# 2230506226.net
KiCad netlist of a schematic drawn in EasyEDA Pro
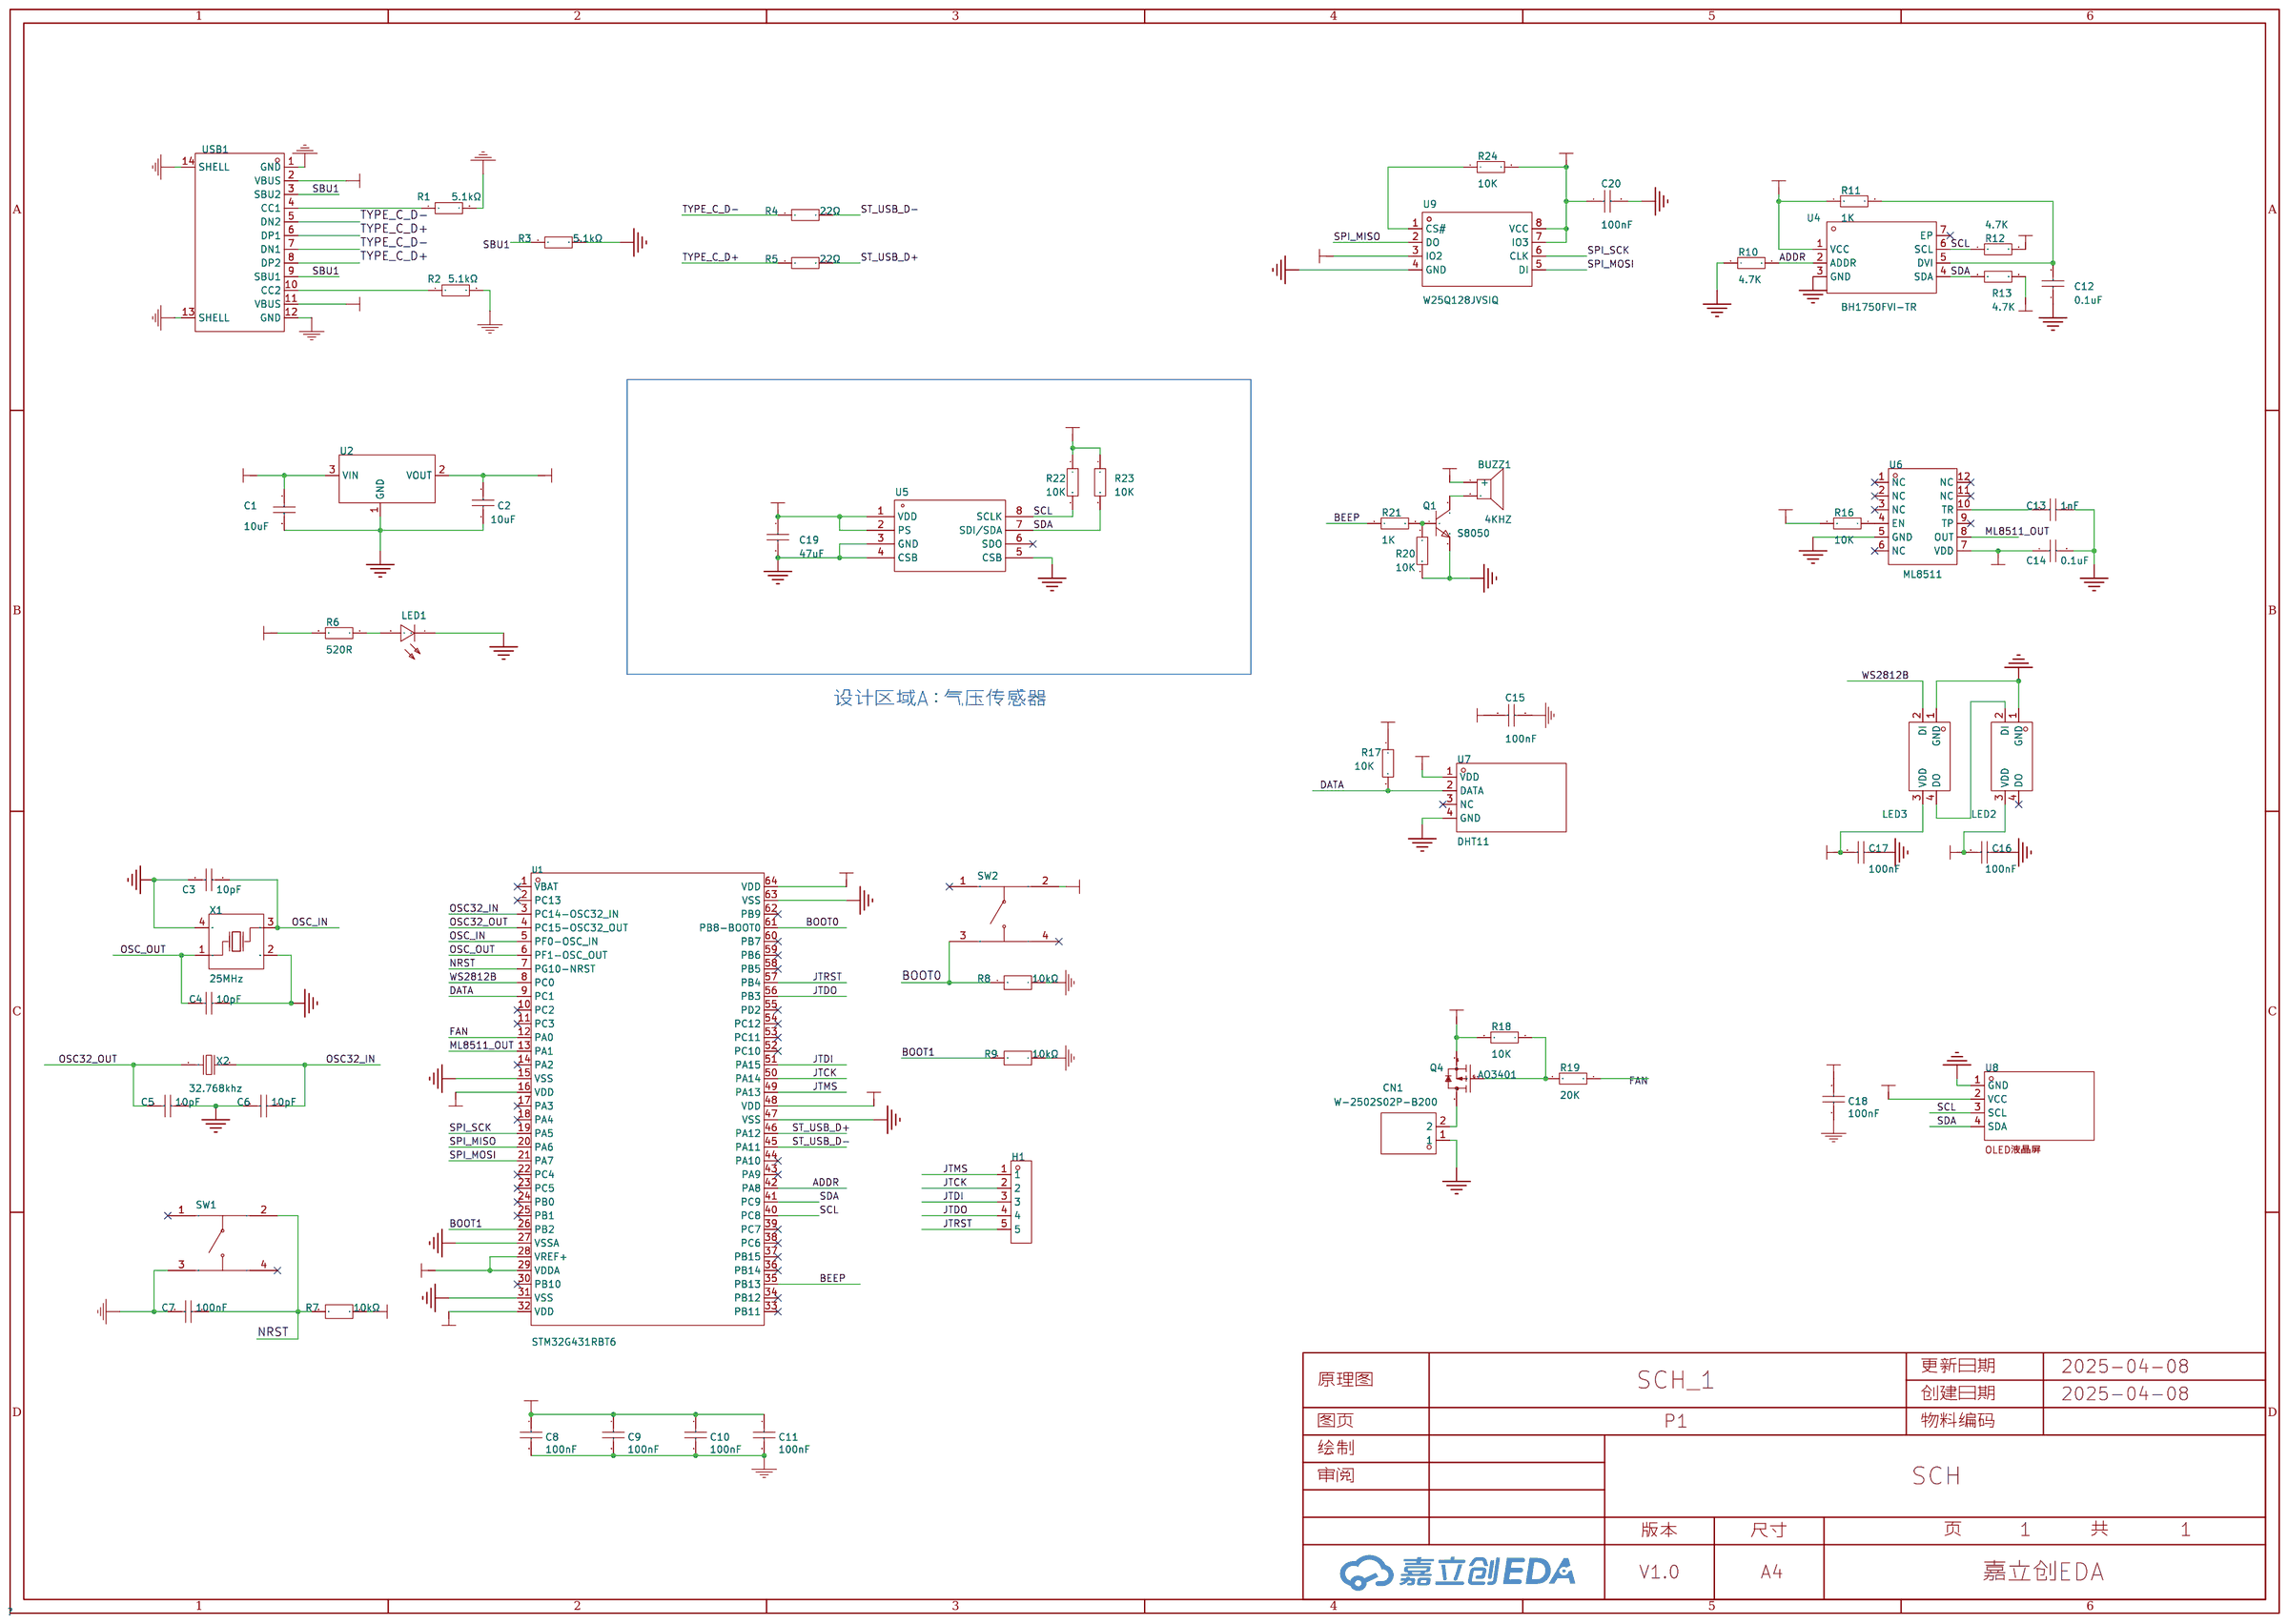
[diagram p0: schematic sheet]

(export (version "E")
  (design (tool "Eeschema 10.0.6"))
  (components
    (comp (ref "BUZZ1")
      (value "4KHZ")
      (footprint "easyedapro:BUZ-TH_BD12.0-P7.60-D0.6-FD")
      (description "驱动方式:有源(内含驱动线路);构造类型:电磁式;频率:2.7kHz;声压(SPL):85dB;")
      (fields (field (name "Manufacturer Part") "TMB12A05") (field (name "Manufacturer") "华能"))
      (libsource (lib "easyedapro") (part "TMB12A05"))
    )
    (comp (ref "C1")
      (value "10uF")
      (footprint "easyedapro:C0805")
      (description "容值:100nF;精度:±10%;额定电压:50V;材质(温度系数):X7R;")
      (fields
        (field (name "Manufacturer Part") "CC0805KRX7R9BB104")
        (field (name "Manufacturer") "YAGEO(国巨)")
      )
      (libsource (lib "easyedapro") (part "CC0805KRX7R9BB104"))
    )
    (comp (ref "C2")
      (value "10uF")
      (footprint "easyedapro:C0805")
      (description "容值:100nF;精度:±10%;额定电压:50V;材质(温度系数):X7R;")
      (fields
        (field (name "Manufacturer Part") "CC0805KRX7R9BB104")
        (field (name "Manufacturer") "YAGEO(国巨)")
      )
      (libsource (lib "easyedapro") (part "CC0805KRX7R9BB104"))
    )
    (comp (ref "C3")
      (value "10pF")
      (footprint "easyedapro:C0805")
      (description "容值:100nF;精度:±10%;额定电压:50V;材质(温度系数):X7R;")
      (fields
        (field (name "Manufacturer Part") "CC0805KRX7R9BB104")
        (field (name "Manufacturer") "YAGEO(国巨)")
      )
      (libsource (lib "easyedapro") (part "CC0805KRX7R9BB104"))
    )
    (comp (ref "C4")
      (value "10pF")
      (footprint "easyedapro:C0805")
      (description "容值:100nF;精度:±10%;额定电压:50V;材质(温度系数):X7R;")
      (fields
        (field (name "Manufacturer Part") "CC0805KRX7R9BB104")
        (field (name "Manufacturer") "YAGEO(国巨)")
      )
      (libsource (lib "easyedapro") (part "CC0805KRX7R9BB104"))
    )
    (comp (ref "C5")
      (value "10pF")
      (footprint "easyedapro:C0805")
      (description "容值:100nF;精度:±10%;额定电压:50V;材质(温度系数):X7R;")
      (fields
        (field (name "Manufacturer Part") "CC0805KRX7R9BB104")
        (field (name "Manufacturer") "YAGEO(国巨)")
      )
      (libsource (lib "easyedapro") (part "CC0805KRX7R9BB104"))
    )
    (comp (ref "C6")
      (value "10pF")
      (footprint "easyedapro:C0805")
      (description "容值:100nF;精度:±10%;额定电压:50V;材质(温度系数):X7R;")
      (fields
        (field (name "Manufacturer Part") "CC0805KRX7R9BB104")
        (field (name "Manufacturer") "YAGEO(国巨)")
      )
      (libsource (lib "easyedapro") (part "CC0805KRX7R9BB104"))
    )
    (comp (ref "C7") (value "100nF") (libsource (lib "easyedapro") (part "100nf")))
    (comp (ref "C8") (value "100nF") (libsource (lib "easyedapro") (part "100nf")))
    (comp (ref "C9") (value "100nF") (libsource (lib "easyedapro") (part "100nf")))
    (comp (ref "C10") (value "100nF") (libsource (lib "easyedapro") (part "100nf")))
    (comp (ref "C11") (value "100nF") (libsource (lib "easyedapro") (part "100nf")))
    (comp (ref "C12")
      (value "0.1uF")
      (footprint "easyedapro:C0805")
      (description "容值:100nF;精度:±10%;额定电压:50V;材质(温度系数):X7R;")
      (fields
        (field (name "Manufacturer Part") "CC0805KRX7R9BB104")
        (field (name "Manufacturer") "YAGEO(国巨)")
      )
      (libsource (lib "easyedapro") (part "CC0805KRX7R9BB104"))
    )
    (comp (ref "C13")
      (value "1nF")
      (footprint "easyedapro:C0805")
      (description "容值:100nF;精度:±10%;额定电压:50V;材质(温度系数):X7R;")
      (fields
        (field (name "Manufacturer Part") "CC0805KRX7R9BB104")
        (field (name "Manufacturer") "YAGEO(国巨)")
      )
      (libsource (lib "easyedapro") (part "CC0805KRX7R9BB104"))
    )
    (comp (ref "C14")
      (value "0.1uF")
      (footprint "easyedapro:C0805")
      (description "容值:100nF;精度:±10%;额定电压:50V;材质(温度系数):X7R;")
      (fields
        (field (name "Manufacturer Part") "CC0805KRX7R9BB104")
        (field (name "Manufacturer") "YAGEO(国巨)")
      )
      (libsource (lib "easyedapro") (part "CC0805KRX7R9BB104"))
    )
    (comp (ref "C15") (value "100nF") (libsource (lib "easyedapro") (part "100nf")))
    (comp (ref "C16")
      (value "100nF")
      (footprint "easyedapro:C0805")
      (description "容值:100nF;精度:±10%;额定电压:50V;材质(温度系数):X7R;")
      (fields
        (field (name "Manufacturer Part") "CC0805KRX7R9BB104")
        (field (name "Manufacturer") "YAGEO(国巨)")
      )
      (libsource (lib "easyedapro") (part "CC0805KRX7R9BB104"))
    )
    (comp (ref "C17")
      (value "100nF")
      (footprint "easyedapro:C0805")
      (description "容值:100nF;精度:±10%;额定电压:50V;材质(温度系数):X7R;")
      (fields
        (field (name "Manufacturer Part") "CC0805KRX7R9BB104")
        (field (name "Manufacturer") "YAGEO(国巨)")
      )
      (libsource (lib "easyedapro") (part "CC0805KRX7R9BB104"))
    )
    (comp (ref "C18") (value "100nF") (libsource (lib "easyedapro") (part "100nf")))
    (comp (ref "C19")
      (value "47uF")
      (footprint "easyedapro:C0805")
      (description "容值:100nF;精度:±10%;额定电压:50V;材质(温度系数):X7R;")
      (fields
        (field (name "Manufacturer Part") "CC0805KRX7R9BB104")
        (field (name "Manufacturer") "YAGEO(国巨)")
      )
      (libsource (lib "easyedapro") (part "CC0805KRX7R9BB104"))
    )
    (comp (ref "C20") (value "100nF") (libsource (lib "easyedapro") (part "100nf")))
    (comp (ref "CN1")
      (value "W-2502S02P-B200")
      (footprint "easyedapro:CONN-TH_2P-P2.54_2501S-2P")
      (description "插针结构:1x2P;间距:2.5mm;安装方式:-;参考系列:XH;总PIN数:2P;排数:1;每排PIN数:2;行距:-;触头材质:黄铜;")
      (fields (field (name "Manufacturer") "Ckmtw(灿科盟)"))
      (libsource (lib "easyedapro") (part "5V直流风扇"))
    )
    (comp (ref "H1")
      (value "~")
      (footprint "easyedapro:5P排针")
      (fields (field (name "Manufacturer Part") "68000-102HLF") (field (name "Manufacturer") "Amphenol ICC"))
      (libsource (lib "easyedapro") (part "5P排针"))
    )
    (comp (ref "LED1")
      (value "NCD0603R1")
      (footprint "easyedapro:LED0603-RD_RED")
      (fields (field (name "Manufacturer") "国星光电"))
      (libsource (lib "easyedapro") (part "FC-DA1608HRK-620D"))
    )
    (comp (ref "LED2")
      (value "XL-5050RGBC-WS2812B")
      (fields (field (name "Manufacturer") "XINGLIGHT(成兴光)"))
      (libsource (lib "easyedapro") (part "XL-3528RGBW-WS2812B"))
    )
    (comp (ref "LED3")
      (value "XL-5050RGBC-WS2812B")
      (fields (field (name "Manufacturer") "XINGLIGHT(成兴光)"))
      (libsource (lib "easyedapro") (part "XL-3528RGBW-WS2812B"))
    )
    (comp (ref "Q1")
      (value "S8050")
      (fields (field (name "Manufacturer") "宏迦橙"))
      (libsource (lib "easyedapro") (part "NPN"))
    )
    (comp (ref "Q4")
      (value "AO3401")
      (footprint "easyedapro:SOT-23-3_L2.9-W1.3-P1.90-LS2.4-BR")
      (fields (field (name "Manufacturer") "Hottech(合科泰)"))
      (libsource (lib "easyedapro") (part "AO3401"))
    )
    (comp (ref "R1") (value "5.1kΩ") (libsource (lib "easyedapro") (part "5.1kΩ")))
    (comp (ref "R2") (value "5.1kΩ") (libsource (lib "easyedapro") (part "5.1kΩ")))
    (comp (ref "R3") (value "5.1kΩ") (libsource (lib "easyedapro") (part "5.1kΩ")))
    (comp (ref "R4")
      (value "22Ω")
      (fields
        (field (name "Manufacturer Part") "0603WAF220JT5E")
        (field (name "Manufacturer") "UNI-ROYAL(厚声)")
      )
      (libsource (lib "easyedapro") (part "电阻"))
    )
    (comp (ref "R5")
      (value "22Ω")
      (fields
        (field (name "Manufacturer Part") "0603WAF220JT5E")
        (field (name "Manufacturer") "UNI-ROYAL(厚声)")
      )
      (libsource (lib "easyedapro") (part "电阻"))
    )
    (comp (ref "R6")
      (value "520R")
      (fields (field (name "Manufacturer Part") "RC0402FR-0710KL") (field (name "Manufacturer") "YAGEO(国巨)"))
      (libsource (lib "easyedapro") (part "电阻"))
    )
    (comp (ref "R7")
      (value "10kΩ")
      (fields (field (name "Manufacturer") "UNI-ROYAL(厚声)"))
      (libsource (lib "easyedapro") (part "10k"))
    )
    (comp (ref "R8")
      (value "10kΩ")
      (fields (field (name "Manufacturer") "UNI-ROYAL(厚声)"))
      (libsource (lib "easyedapro") (part "10k"))
    )
    (comp (ref "R9")
      (value "10kΩ")
      (fields (field (name "Manufacturer") "UNI-ROYAL(厚声)"))
      (libsource (lib "easyedapro") (part "10k"))
    )
    (comp (ref "R10")
      (value "4.7K")
      (footprint "easyedapro:R0805")
      (libsource (lib "easyedapro") (part "电阻"))
    )
    (comp (ref "R11") (value "1K") (footprint "easyedapro:R0805") (libsource (lib "easyedapro") (part "电阻")))
    (comp (ref "R12")
      (value "4.7K")
      (footprint "easyedapro:R0805")
      (libsource (lib "easyedapro") (part "电阻"))
    )
    (comp (ref "R13")
      (value "4.7K")
      (footprint "easyedapro:R0805")
      (libsource (lib "easyedapro") (part "电阻"))
    )
    (comp (ref "R16")
      (value "10K")
      (fields (field (name "Manufacturer Part") "RC0402FR-0710KL") (field (name "Manufacturer") "YAGEO(国巨)"))
      (libsource (lib "easyedapro") (part "电阻"))
    )
    (comp (ref "R17") (value "10K") (footprint "easyedapro:R0805") (libsource (lib "easyedapro") (part "电阻")))
    (comp (ref "R18") (value "10K") (footprint "easyedapro:R0805") (libsource (lib "easyedapro") (part "电阻")))
    (comp (ref "R19") (value "20K") (footprint "easyedapro:R0805") (libsource (lib "easyedapro") (part "电阻")))
    (comp (ref "R20") (value "10K") (footprint "easyedapro:R0805") (libsource (lib "easyedapro") (part "电阻")))
    (comp (ref "R21") (value "1K") (footprint "easyedapro:R0805") (libsource (lib "easyedapro") (part "电阻")))
    (comp (ref "R22") (value "10K") (footprint "easyedapro:R0805") (libsource (lib "easyedapro") (part "电阻")))
    (comp (ref "R23") (value "10K") (footprint "easyedapro:R0805") (libsource (lib "easyedapro") (part "电阻")))
    (comp (ref "R24") (value "10K") (footprint "easyedapro:R0805") (libsource (lib "easyedapro") (part "电阻")))
    (comp (ref "SW1")
      (value "TSA017A2540A07")
      (footprint "easyedapro:SW-SMD_4P-L4.2-W3.4-P2.15-LS5.2")
      (fields (field (name "Manufacturer") "BZCN(博众电气)"))
      (libsource (lib "easyedapro") (part "TSA017A2540A07"))
    )
    (comp (ref "SW2")
      (value "TSA017A2540A07")
      (footprint "easyedapro:SW-SMD_4P-L4.2-W3.4-P2.15-LS5.2")
      (fields (field (name "Manufacturer") "BZCN(博众电气)"))
      (libsource (lib "easyedapro") (part "TSA017A2540A07"))
    )
    (comp (ref "U1")
      (value "STM32G431RBT6")
      (footprint "easyedapro:LQFP-64_L10.0-W10.0-P0.50-LS12.0-BL")
      (description "CPU内核:ARM-M系列;程序存储容量:128KB;GPIO端口数量:52;工作电压范围:1.71V~3.6V;CPU最大主频:170MHz;")
      (fields (field (name "Manufacturer") "ST(意法半导体)"))
      (libsource (lib "easyedapro") (part "STM32G431RBT6"))
    )
    (comp (ref "U2")
      (value "AMS1117-3.3(XBLW)")
      (footprint "easyedapro:SOT-223-3_L6.5-W3.4-P2.30-LS7.0-BR-1")
      (description "最大输入电压:15V;输出电压:3.3V;最大输出电流:1A;电源纹波抑制比(PSRR):60dB;")
      (fields (field (name "Manufacturer") "XBLW(芯伯乐)"))
      (libsource (lib "easyedapro") (part "AMS1117-3.3(XBLW)_C18906017"))
    )
    (comp (ref "U4")
      (value "BH1750FVI-TR")
      (footprint "easyedapro:WSOF-6_L2.6-W1.6-P0.50-TL-EP")
      (description "检测颜色:-;接口类型:I2C;分辨率(位):16;")
      (fields (field (name "Manufacturer") "ROHM(罗姆)"))
      (libsource (lib "easyedapro") (part "BH1750FVI-TR"))
    )
    (comp (ref "U5") (value "~") (libsource (lib "easyedapro") (part "IC-8")))
    (comp (ref "U6")
      (value "ML8511")
      (footprint "easyedapro:DFN-12_L4.0-W3.7-P1.00-TL")
      (fields (field (name "Manufacturer") "ROHM(罗姆)"))
      (libsource (lib "easyedapro") (part "ML8511_REFBOARD"))
    )
    (comp (ref "U7")
      (value "DHT11")
      (footprint "easyedapro:SENSOR-TH_DHT11")
      (description "新款电容式数字温湿度传感器,老款已停产16.1x12.6x5.8mm")
      (fields (field (name "Manufacturer") "广州奥松"))
      (libsource (lib "easyedapro") (part "DHT11"))
    )
    (comp (ref "U8")
      (value "~")
      (footprint "easyedapro:CONN-TH_4P-P2.54_POGO-4P")
      (description "OLED液晶屏")
      (libsource (lib "easyedapro") (part "OLED液晶屏"))
    )
    (comp (ref "U9")
      (value "W25Q128JVSIQ")
      (footprint "easyedapro:SOIC-8_L5.3-W5.3-P1.27-LS8.0-BL")
      (description "存储器构架(格式):FLASH;存储器接口类型:SPI - Dual/Quad I/O;存储器容量:128Mb (16M x 8);")
      (fields (field (name "Manufacturer") "WINBOND(华邦)"))
      (libsource (lib "easyedapro") (part "W25Q128JVSIQTR"))
    )
    (comp (ref "USB1") (value "TYPE-C 16PIN 2MD(073)") (libsource (lib "easyedapro") (part "type-c 16pin")))
    (comp (ref "X1")
      (value "25MHz")
      (footprint "easyedapro:OSC-SMD_4P-L3.2-W2.5-BL")
      (description "晶振类型:贴片晶振;频率:25MHz;常温频差:±10ppm;外接负载电容:12pF;频率稳定度(全温):±20ppm;")
      (fields (field (name "Manufacturer Part") "X322525MOB4SI") (field (name "Manufacturer") "YXC(扬兴晶振)"))
      (libsource (lib "easyedapro") (part "X322525MOB4SI"))
    )
    (comp (ref "X2")
      (value "32.768kHz")
      (footprint "easyedapro:FC-135R_L3.2-W1.5")
      (description "频率:32.768kHz;晶振类型:贴片无源晶振;负载电容:12.5pF;等效串联电阻(ESR):70kΩ;频率公差:±20ppm;频率稳定度:-;工作温度:-40°C~+85°C;")
      (fields (field (name "Manufacturer Part") "Q13FC1350000400") (field (name "Manufacturer") "EPSON(爱普生)"))
      (libsource (lib "easyedapro") (part "Q13FC1350000400"))
    )
  )
  (nets
    (net (code "1") (name "/ADDR") (class "Default")
      (node (ref "R10") (pin "2") (pinfunction "2_2") (pintype "input"))
      (node (ref "U1") (pin "42") (pinfunction "PA8_42") (pintype "input"))
      (node (ref "U4") (pin "2") (pinfunction "ADDR_2") (pintype "unspecified"))
    )
    (net (code "2") (name "/BEEP") (class "Default")
      (node (ref "R21") (pin "1") (pinfunction "1_1") (pintype "input"))
      (node (ref "U1") (pin "35") (pinfunction "PB13_35") (pintype "input"))
    )
    (net (code "3") (name "/BOOT0") (class "Default")
      (node (ref "R8") (pin "2") (pinfunction "2_2") (pintype "unspecified"))
      (node (ref "SW2") (pin "3") (pinfunction "3_3") (pintype "unspecified"))
      (node (ref "U1") (pin "61") (pinfunction "PB8-BOOT0_61") (pintype "input"))
    )
    (net (code "4") (name "/BOOT1") (class "Default")
      (node (ref "R9") (pin "2") (pinfunction "2_2") (pintype "unspecified"))
      (node (ref "U1") (pin "26") (pinfunction "PB2_26") (pintype "input"))
    )
    (net (code "5") (name "/DATA") (class "Default")
      (node (ref "R17") (pin "2") (pinfunction "2_2") (pintype "input"))
      (node (ref "U1") (pin "9") (pinfunction "PC1_9") (pintype "input"))
      (node (ref "U7") (pin "2") (pinfunction "DATA_2") (pintype "unspecified"))
    )
    (net (code "6") (name "/FAN") (class "Default")
      (node (ref "R19") (pin "1") (pinfunction "1_1") (pintype "input"))
      (node (ref "U1") (pin "12") (pinfunction "PA0_12") (pintype "input"))
    )
    (net (code "7") (name "/JTCK") (class "Default")
      (node (ref "H1") (pin "2") (pinfunction "2_2") (pintype "input"))
      (node (ref "U1") (pin "50") (pinfunction "PA14_50") (pintype "input"))
    )
    (net (code "8") (name "/JTDI") (class "Default")
      (node (ref "H1") (pin "3") (pinfunction "3_3") (pintype "input"))
      (node (ref "U1") (pin "51") (pinfunction "PA15_51") (pintype "input"))
    )
    (net (code "9") (name "/JTDO") (class "Default")
      (node (ref "H1") (pin "4") (pinfunction "4_4") (pintype "input"))
      (node (ref "U1") (pin "56") (pinfunction "PB3_56") (pintype "input"))
    )
    (net (code "10") (name "/JTMS") (class "Default")
      (node (ref "H1") (pin "1") (pinfunction "1_1") (pintype "input"))
      (node (ref "U1") (pin "49") (pinfunction "PA13_49") (pintype "input"))
    )
    (net (code "11") (name "/JTRST") (class "Default")
      (node (ref "H1") (pin "5") (pinfunction "5_5") (pintype "input"))
      (node (ref "U1") (pin "57") (pinfunction "PB4_57") (pintype "input"))
    )
    (net (code "12") (name "/ML8511_OUT") (class "Default")
      (node (ref "U1") (pin "13") (pinfunction "PA1_13") (pintype "input"))
      (node (ref "U6") (pin "8") (pinfunction "OUT_8") (pintype "unspecified"))
    )
    (net (code "13") (name "/NRST") (class "Default")
      (node (ref "C7") (pin "1") (pinfunction "1_1") (pintype "input"))
      (node (ref "R7") (pin "2") (pinfunction "2_2") (pintype "unspecified"))
      (node (ref "SW1") (pin "2") (pinfunction "2_2") (pintype "unspecified"))
      (node (ref "U1") (pin "7") (pinfunction "PG10-NRST_7") (pintype "input"))
    )
    (net (code "14") (name "/OSC32_IN") (class "Default")
      (node (ref "C6") (pin "1") (pinfunction "1_1") (pintype "input"))
      (node (ref "U1") (pin "3") (pinfunction "PC14-OSC32_IN_3") (pintype "input"))
      (node (ref "X2") (pin "2") (pinfunction "2_2") (pintype "input"))
    )
    (net (code "15") (name "/OSC32_OUT") (class "Default")
      (node (ref "C5") (pin "2") (pinfunction "2_2") (pintype "input"))
      (node (ref "U1") (pin "4") (pinfunction "PC15-OSC32_OUT_4") (pintype "input"))
      (node (ref "X2") (pin "1") (pinfunction "1_1") (pintype "input"))
    )
    (net (code "16") (name "/OSC_IN") (class "Default")
      (node (ref "C3") (pin "2") (pinfunction "2_2") (pintype "input"))
      (node (ref "U1") (pin "5") (pinfunction "PF0-OSC_IN_5") (pintype "input"))
      (node (ref "X1") (pin "3") (pinfunction "OSC2_3") (pintype "unspecified"))
    )
    (net (code "17") (name "/OSC_OUT") (class "Default")
      (node (ref "C4") (pin "2") (pinfunction "2_2") (pintype "input"))
      (node (ref "U1") (pin "6") (pinfunction "PF1-OSC_OUT_6") (pintype "input"))
      (node (ref "X1") (pin "1") (pinfunction "OSC1_1") (pintype "unspecified"))
    )
    (net (code "18") (name "/SBU1") (class "Default")
      (node (ref "R3") (pin "1") (pinfunction "1_1") (pintype "input"))
      (node (ref "USB1") (pin "3") (pinfunction "SBU2_3") (pintype "unspecified"))
      (node (ref "USB1") (pin "9") (pinfunction "SBU1_9") (pintype "unspecified"))
    )
    (net (code "19") (name "/SCL") (class "Default")
      (node (ref "R12") (pin "1") (pinfunction "1_1") (pintype "input"))
      (node (ref "R22") (pin "2") (pinfunction "2_2") (pintype "input"))
      (node (ref "U1") (pin "40") (pinfunction "PC8_40") (pintype "input"))
      (node (ref "U4") (pin "6") (pinfunction "SCL_6") (pintype "unspecified"))
      (node (ref "U5") (pin "8") (pinfunction "SCLK_8") (pintype "input"))
      (node (ref "U8") (pin "3") (pinfunction "SCL_3") (pintype "unspecified"))
    )
    (net (code "20") (name "/SDA") (class "Default")
      (node (ref "R13") (pin "1") (pinfunction "1_1") (pintype "input"))
      (node (ref "R23") (pin "2") (pinfunction "2_2") (pintype "input"))
      (node (ref "U1") (pin "41") (pinfunction "PC9_41") (pintype "input"))
      (node (ref "U4") (pin "4") (pinfunction "SDA_4") (pintype "unspecified"))
      (node (ref "U5") (pin "7") (pinfunction "SDI/SDA_7") (pintype "input"))
      (node (ref "U8") (pin "4") (pinfunction "SDA_4") (pintype "unspecified"))
    )
    (net (code "21") (name "/SPI_MISO") (class "Default")
      (node (ref "U1") (pin "20") (pinfunction "PA6_20") (pintype "input"))
      (node (ref "U9") (pin "2") (pinfunction "DO_2") (pintype "input"))
    )
    (net (code "22") (name "/SPI_MOSI") (class "Default")
      (node (ref "U1") (pin "21") (pinfunction "PA7_21") (pintype "input"))
      (node (ref "U9") (pin "5") (pinfunction "DI_5") (pintype "input"))
    )
    (net (code "23") (name "/SPI_SCK") (class "Default")
      (node (ref "U1") (pin "19") (pinfunction "PA5_19") (pintype "input"))
      (node (ref "U9") (pin "6") (pinfunction "CLK_6") (pintype "input"))
    )
    (net (code "24") (name "/ST_USB_D+") (class "Default")
      (node (ref "R5") (pin "2") (pinfunction "2_2") (pintype "input"))
      (node (ref "U1") (pin "46") (pinfunction "PA12_46") (pintype "input"))
    )
    (net (code "25") (name "/ST_USB_D-") (class "Default")
      (node (ref "R4") (pin "2") (pinfunction "2_2") (pintype "input"))
      (node (ref "U1") (pin "45") (pinfunction "PA11_45") (pintype "input"))
    )
    (net (code "26") (name "/TYPE_C_D+") (class "Default")
      (node (ref "R5") (pin "1") (pinfunction "1_1") (pintype "input"))
      (node (ref "USB1") (pin "6") (pinfunction "DP1_6") (pintype "unspecified"))
      (node (ref "USB1") (pin "8") (pinfunction "DP2_8") (pintype "unspecified"))
    )
    (net (code "27") (name "/TYPE_C_D-") (class "Default")
      (node (ref "R4") (pin "1") (pinfunction "1_1") (pintype "input"))
      (node (ref "USB1") (pin "5") (pinfunction "DN2_5") (pintype "unspecified"))
      (node (ref "USB1") (pin "7") (pinfunction "DN1_7") (pintype "unspecified"))
    )
    (net (code "28") (name "/WS2812B") (class "Default")
      (node (ref "LED3") (pin "2") (pinfunction "DI_2") (pintype "input"))
      (node (ref "U1") (pin "8") (pinfunction "PC0_8") (pintype "input"))
    )
    (net (code "29") (name "3.3V") (class "Default")
      (node (ref "BUZZ1") (pin "1") (pinfunction "+_1") (pintype "unspecified"))
      (node (ref "C10") (pin "1") (pinfunction "1_1") (pintype "input"))
      (node (ref "C11") (pin "1") (pinfunction "1_1") (pintype "input"))
      (node (ref "C14") (pin "1") (pinfunction "1_1") (pintype "input"))
      (node (ref "C15") (pin "1") (pinfunction "1_1") (pintype "input"))
      (node (ref "C18") (pin "1") (pinfunction "1_1") (pintype "input"))
      (node (ref "C19") (pin "1") (pinfunction "1_1") (pintype "input"))
      (node (ref "C2") (pin "2") (pinfunction "2_2") (pintype "input"))
      (node (ref "C20") (pin "1") (pinfunction "1_1") (pintype "input"))
      (node (ref "C8") (pin "1") (pinfunction "1_1") (pintype "input"))
      (node (ref "C9") (pin "1") (pinfunction "1_1") (pintype "input"))
      (node (ref "R11") (pin "1") (pinfunction "1_1") (pintype "input"))
      (node (ref "R12") (pin "2") (pinfunction "2_2") (pintype "input"))
      (node (ref "R13") (pin "2") (pinfunction "2_2") (pintype "input"))
      (node (ref "R16") (pin "2") (pinfunction "2_2") (pintype "input"))
      (node (ref "R17") (pin "1") (pinfunction "1_1") (pintype "input"))
      (node (ref "R22") (pin "1") (pinfunction "1_1") (pintype "input"))
      (node (ref "R23") (pin "1") (pinfunction "1_1") (pintype "input"))
      (node (ref "R24") (pin "2") (pinfunction "2_2") (pintype "input"))
      (node (ref "R6") (pin "2") (pinfunction "2_2") (pintype "input"))
      (node (ref "R7") (pin "1") (pinfunction "1_1") (pintype "unspecified"))
      (node (ref "SW2") (pin "2") (pinfunction "2_2") (pintype "unspecified"))
      (node (ref "U1") (pin "16") (pinfunction "VDD_16") (pintype "input"))
      (node (ref "U1") (pin "28") (pinfunction "VREF+_28") (pintype "input"))
      (node (ref "U1") (pin "29") (pinfunction "VDDA_29") (pintype "input"))
      (node (ref "U1") (pin "32") (pinfunction "VDD_32") (pintype "input"))
      (node (ref "U1") (pin "48") (pinfunction "VDD_48") (pintype "input"))
      (node (ref "U1") (pin "64") (pinfunction "VDD_64") (pintype "input"))
      (node (ref "U2") (pin "2") (pinfunction "VOUT_2") (pintype "unspecified"))
      (node (ref "U4") (pin "1") (pinfunction "VCC_1") (pintype "unspecified"))
      (node (ref "U5") (pin "1") (pinfunction "VDD_1") (pintype "input"))
      (node (ref "U5") (pin "2") (pinfunction "PS_2") (pintype "input"))
      (node (ref "U6") (pin "7") (pinfunction "VDD_7") (pintype "unspecified"))
      (node (ref "U7") (pin "1") (pinfunction "VDD_1") (pintype "unspecified"))
      (node (ref "U8") (pin "2") (pinfunction "VCC_2") (pintype "unspecified"))
      (node (ref "U9") (pin "3") (pinfunction "IO2_3") (pintype "input"))
      (node (ref "U9") (pin "7") (pinfunction "IO3_7") (pintype "input"))
      (node (ref "U9") (pin "8") (pinfunction "VCC_8") (pintype "input"))
    )
    (net (code "30") (name "5V") (class "Default")
      (node (ref "C1") (pin "1") (pinfunction "1_1") (pintype "input"))
      (node (ref "C16") (pin "2") (pinfunction "2_2") (pintype "input"))
      (node (ref "C17") (pin "2") (pinfunction "2_2") (pintype "input"))
      (node (ref "LED2") (pin "3") (pinfunction "VDD_3") (pintype "input"))
      (node (ref "LED3") (pin "3") (pinfunction "VDD_3") (pintype "input"))
      (node (ref "Q4") (pin "2") (pinfunction "S_2") (pintype "unspecified"))
      (node (ref "R18") (pin "2") (pinfunction "2_2") (pintype "input"))
      (node (ref "U2") (pin "3") (pinfunction "VIN_3") (pintype "unspecified"))
      (node (ref "USB1") (pin "11") (pinfunction "VBUS_11") (pintype "unspecified"))
      (node (ref "USB1") (pin "2") (pinfunction "VBUS_2") (pintype "unspecified"))
    )
    (net (code "31") (name "GND") (class "Default")
      (node (ref "C1") (pin "2") (pinfunction "2_2") (pintype "input"))
      (node (ref "C10") (pin "2") (pinfunction "2_2") (pintype "input"))
      (node (ref "C11") (pin "2") (pinfunction "2_2") (pintype "input"))
      (node (ref "C12") (pin "1") (pinfunction "1_1") (pintype "input"))
      (node (ref "C13") (pin "1") (pinfunction "1_1") (pintype "input"))
      (node (ref "C14") (pin "2") (pinfunction "2_2") (pintype "input"))
      (node (ref "C15") (pin "2") (pinfunction "2_2") (pintype "input"))
      (node (ref "C16") (pin "1") (pinfunction "1_1") (pintype "input"))
      (node (ref "C17") (pin "1") (pinfunction "1_1") (pintype "input"))
      (node (ref "C18") (pin "2") (pinfunction "2_2") (pintype "input"))
      (node (ref "C19") (pin "2") (pinfunction "2_2") (pintype "input"))
      (node (ref "C2") (pin "1") (pinfunction "1_1") (pintype "input"))
      (node (ref "C20") (pin "2") (pinfunction "2_2") (pintype "input"))
      (node (ref "C3") (pin "1") (pinfunction "1_1") (pintype "input"))
      (node (ref "C4") (pin "1") (pinfunction "1_1") (pintype "input"))
      (node (ref "C5") (pin "1") (pinfunction "1_1") (pintype "input"))
      (node (ref "C6") (pin "2") (pinfunction "2_2") (pintype "input"))
      (node (ref "C7") (pin "2") (pinfunction "2_2") (pintype "input"))
      (node (ref "C8") (pin "2") (pinfunction "2_2") (pintype "input"))
      (node (ref "C9") (pin "2") (pinfunction "2_2") (pintype "input"))
      (node (ref "CN1") (pin "1") (pinfunction "1_1") (pintype "unspecified"))
      (node (ref "LED1") (pin "1") (pinfunction "K_1") (pintype "input"))
      (node (ref "LED2") (pin "1") (pinfunction "GND_1") (pintype "input"))
      (node (ref "LED3") (pin "1") (pinfunction "GND_1") (pintype "input"))
      (node (ref "Q1") (pin "2") (pinfunction "2_2") (pintype "unspecified"))
      (node (ref "R1") (pin "2") (pinfunction "2_2") (pintype "input"))
      (node (ref "R10") (pin "1") (pinfunction "1_1") (pintype "input"))
      (node (ref "R2") (pin "2") (pinfunction "2_2") (pintype "input"))
      (node (ref "R20") (pin "2") (pinfunction "2_2") (pintype "input"))
      (node (ref "R3") (pin "2") (pinfunction "2_2") (pintype "input"))
      (node (ref "R8") (pin "1") (pinfunction "1_1") (pintype "unspecified"))
      (node (ref "R9") (pin "1") (pinfunction "1_1") (pintype "unspecified"))
      (node (ref "SW1") (pin "3") (pinfunction "3_3") (pintype "unspecified"))
      (node (ref "U1") (pin "15") (pinfunction "VSS_15") (pintype "input"))
      (node (ref "U1") (pin "27") (pinfunction "VSSA_27") (pintype "input"))
      (node (ref "U1") (pin "31") (pinfunction "VSS_31") (pintype "input"))
      (node (ref "U1") (pin "47") (pinfunction "VSS_47") (pintype "input"))
      (node (ref "U1") (pin "63") (pinfunction "VSS_63") (pintype "input"))
      (node (ref "U2") (pin "1") (pinfunction "GND_1") (pintype "unspecified"))
      (node (ref "U4") (pin "3") (pinfunction "GND_3") (pintype "unspecified"))
      (node (ref "U5") (pin "3") (pinfunction "GND_3") (pintype "input"))
      (node (ref "U5") (pin "4") (pinfunction "CSB_4") (pintype "input"))
      (node (ref "U5") (pin "5") (pinfunction "CSB_5") (pintype "input"))
      (node (ref "U6") (pin "5") (pinfunction "GND_5") (pintype "unspecified"))
      (node (ref "U7") (pin "4") (pinfunction "GND_4") (pintype "unspecified"))
      (node (ref "U8") (pin "1") (pinfunction "GND_1") (pintype "unspecified"))
      (node (ref "U9") (pin "4") (pinfunction "GND_4") (pintype "input"))
      (node (ref "USB1") (pin "1") (pinfunction "GND_1") (pintype "unspecified"))
      (node (ref "USB1") (pin "12") (pinfunction "GND_12") (pintype "unspecified"))
      (node (ref "USB1") (pin "13") (pinfunction "SHELL_13") (pintype "unspecified"))
      (node (ref "USB1") (pin "14") (pinfunction "SHELL_14") (pintype "unspecified"))
      (node (ref "X1") (pin "2") (pinfunction "GND_2") (pintype "unspecified"))
      (node (ref "X1") (pin "4") (pinfunction "GND_4") (pintype "unspecified"))
    )
    (net (code "32") (name "Net-(BUZZ1-Pad2)") (class "Default")
      (node (ref "BUZZ1") (pin "2") (pinfunction "2_2") (pintype "unspecified"))
      (node (ref "Q1") (pin "3") (pinfunction "3_3") (pintype "unspecified"))
    )
    (net (code "33") (name "Net-(LED1-A)") (class "Default")
      (node (ref "LED1") (pin "2") (pinfunction "A_2") (pintype "input"))
      (node (ref "R6") (pin "1") (pinfunction "1_1") (pintype "input"))
    )
    (net (code "34") (name "Net-(LED2-DI)") (class "Default")
      (node (ref "LED2") (pin "2") (pinfunction "DI_2") (pintype "input"))
      (node (ref "LED3") (pin "4") (pinfunction "DO_4") (pintype "input"))
    )
    (net (code "35") (name "Net-(Q1-Pad1)") (class "Default")
      (node (ref "Q1") (pin "1") (pinfunction "1_1") (pintype "unspecified"))
      (node (ref "R20") (pin "1") (pinfunction "1_1") (pintype "input"))
      (node (ref "R21") (pin "2") (pinfunction "2_2") (pintype "input"))
    )
    (net (code "36") (name "Net-(Q4-D)") (class "Default")
      (node (ref "CN1") (pin "2") (pinfunction "2_2") (pintype "unspecified"))
      (node (ref "Q4") (pin "3") (pinfunction "D_3") (pintype "unspecified"))
    )
    (net (code "37") (name "Net-(Q4-G)") (class "Default")
      (node (ref "Q4") (pin "1") (pinfunction "G_1") (pintype "unspecified"))
      (node (ref "R18") (pin "1") (pinfunction "1_1") (pintype "input"))
      (node (ref "R19") (pin "2") (pinfunction "2_2") (pintype "input"))
    )
    (net (code "38") (name "Net-(U4-DVI)") (class "Default")
      (node (ref "C12") (pin "2") (pinfunction "2_2") (pintype "input"))
      (node (ref "R11") (pin "2") (pinfunction "2_2") (pintype "input"))
      (node (ref "U4") (pin "5") (pinfunction "DVI_5") (pintype "unspecified"))
    )
    (net (code "39") (name "Net-(U6-EN)") (class "Default")
      (node (ref "R16") (pin "1") (pinfunction "1_1") (pintype "input"))
      (node (ref "U6") (pin "4") (pinfunction "EN_4") (pintype "unspecified"))
    )
    (net (code "40") (name "Net-(U6-TR)") (class "Default")
      (node (ref "C13") (pin "2") (pinfunction "2_2") (pintype "input"))
      (node (ref "U6") (pin "10") (pinfunction "TR_10") (pintype "unspecified"))
    )
    (net (code "41") (name "Net-(U9-CS#)") (class "Default")
      (node (ref "R24") (pin "1") (pinfunction "1_1") (pintype "input"))
      (node (ref "U9") (pin "1") (pinfunction "CS#_1") (pintype "input"))
    )
    (net (code "42") (name "Net-(USB1-CC1)") (class "Default")
      (node (ref "R1") (pin "1") (pinfunction "1_1") (pintype "input"))
      (node (ref "USB1") (pin "4") (pinfunction "CC1_4") (pintype "unspecified"))
    )
    (net (code "43") (name "Net-(USB1-CC2)") (class "Default")
      (node (ref "R2") (pin "1") (pinfunction "1_1") (pintype "input"))
      (node (ref "USB1") (pin "10") (pinfunction "CC2_10") (pintype "unspecified"))
    )
    (net (code "44") (name "unconnected-(LED2-DO-Pad4)") (class "Default")
      (node (ref "LED2") (pin "4") (pinfunction "DO_4") (pintype "input+no_connect"))
    )
    (net (code "45") (name "unconnected-(SW1-Pad1)") (class "Default")
      (node (ref "SW1") (pin "1") (pinfunction "1_1") (pintype "unspecified+no_connect"))
    )
    (net (code "46") (name "unconnected-(SW1-Pad4)") (class "Default")
      (node (ref "SW1") (pin "4") (pinfunction "4_4") (pintype "unspecified+no_connect"))
    )
    (net (code "47") (name "unconnected-(SW2-Pad1)") (class "Default")
      (node (ref "SW2") (pin "1") (pinfunction "1_1") (pintype "unspecified+no_connect"))
    )
    (net (code "48") (name "unconnected-(SW2-Pad4)") (class "Default")
      (node (ref "SW2") (pin "4") (pinfunction "4_4") (pintype "unspecified+no_connect"))
    )
    (net (code "49") (name "unconnected-(U1-PA2-Pad14)") (class "Default")
      (node (ref "U1") (pin "14") (pinfunction "PA2_14") (pintype "input+no_connect"))
    )
    (net (code "50") (name "unconnected-(U1-PA3-Pad17)") (class "Default")
      (node (ref "U1") (pin "17") (pinfunction "PA3_17") (pintype "input+no_connect"))
    )
    (net (code "51") (name "unconnected-(U1-PA4-Pad18)") (class "Default")
      (node (ref "U1") (pin "18") (pinfunction "PA4_18") (pintype "input+no_connect"))
    )
    (net (code "52") (name "unconnected-(U1-PA9-Pad43)") (class "Default")
      (node (ref "U1") (pin "43") (pinfunction "PA9_43") (pintype "input+no_connect"))
    )
    (net (code "53") (name "unconnected-(U1-PA10-Pad44)") (class "Default")
      (node (ref "U1") (pin "44") (pinfunction "PA10_44") (pintype "input+no_connect"))
    )
    (net (code "54") (name "unconnected-(U1-PB0-Pad24)") (class "Default")
      (node (ref "U1") (pin "24") (pinfunction "PB0_24") (pintype "input+no_connect"))
    )
    (net (code "55") (name "unconnected-(U1-PB1-Pad25)") (class "Default")
      (node (ref "U1") (pin "25") (pinfunction "PB1_25") (pintype "input+no_connect"))
    )
    (net (code "56") (name "unconnected-(U1-PB5-Pad58)") (class "Default")
      (node (ref "U1") (pin "58") (pinfunction "PB5_58") (pintype "input+no_connect"))
    )
    (net (code "57") (name "unconnected-(U1-PB6-Pad59)") (class "Default")
      (node (ref "U1") (pin "59") (pinfunction "PB6_59") (pintype "input+no_connect"))
    )
    (net (code "58") (name "unconnected-(U1-PB7-Pad60)") (class "Default")
      (node (ref "U1") (pin "60") (pinfunction "PB7_60") (pintype "input+no_connect"))
    )
    (net (code "59") (name "unconnected-(U1-PB9-Pad62)") (class "Default")
      (node (ref "U1") (pin "62") (pinfunction "PB9_62") (pintype "input+no_connect"))
    )
    (net (code "60") (name "unconnected-(U1-PB10-Pad30)") (class "Default")
      (node (ref "U1") (pin "30") (pinfunction "PB10_30") (pintype "input+no_connect"))
    )
    (net (code "61") (name "unconnected-(U1-PB11-Pad33)") (class "Default")
      (node (ref "U1") (pin "33") (pinfunction "PB11_33") (pintype "input+no_connect"))
    )
    (net (code "62") (name "unconnected-(U1-PB12-Pad34)") (class "Default")
      (node (ref "U1") (pin "34") (pinfunction "PB12_34") (pintype "input+no_connect"))
    )
    (net (code "63") (name "unconnected-(U1-PB14-Pad36)") (class "Default")
      (node (ref "U1") (pin "36") (pinfunction "PB14_36") (pintype "input+no_connect"))
    )
    (net (code "64") (name "unconnected-(U1-PB15-Pad37)") (class "Default")
      (node (ref "U1") (pin "37") (pinfunction "PB15_37") (pintype "input+no_connect"))
    )
    (net (code "65") (name "unconnected-(U1-PC2-Pad10)") (class "Default")
      (node (ref "U1") (pin "10") (pinfunction "PC2_10") (pintype "input+no_connect"))
    )
    (net (code "66") (name "unconnected-(U1-PC3-Pad11)") (class "Default")
      (node (ref "U1") (pin "11") (pinfunction "PC3_11") (pintype "input+no_connect"))
    )
    (net (code "67") (name "unconnected-(U1-PC4-Pad22)") (class "Default")
      (node (ref "U1") (pin "22") (pinfunction "PC4_22") (pintype "input+no_connect"))
    )
    (net (code "68") (name "unconnected-(U1-PC5-Pad23)") (class "Default")
      (node (ref "U1") (pin "23") (pinfunction "PC5_23") (pintype "input+no_connect"))
    )
    (net (code "69") (name "unconnected-(U1-PC6-Pad38)") (class "Default")
      (node (ref "U1") (pin "38") (pinfunction "PC6_38") (pintype "input+no_connect"))
    )
    (net (code "70") (name "unconnected-(U1-PC7-Pad39)") (class "Default")
      (node (ref "U1") (pin "39") (pinfunction "PC7_39") (pintype "input+no_connect"))
    )
    (net (code "71") (name "unconnected-(U1-PC10-Pad52)") (class "Default")
      (node (ref "U1") (pin "52") (pinfunction "PC10_52") (pintype "input+no_connect"))
    )
    (net (code "72") (name "unconnected-(U1-PC11-Pad53)") (class "Default")
      (node (ref "U1") (pin "53") (pinfunction "PC11_53") (pintype "input+no_connect"))
    )
    (net (code "73") (name "unconnected-(U1-PC12-Pad54)") (class "Default")
      (node (ref "U1") (pin "54") (pinfunction "PC12_54") (pintype "input+no_connect"))
    )
    (net (code "74") (name "unconnected-(U1-PC13-Pad2)") (class "Default")
      (node (ref "U1") (pin "2") (pinfunction "PC13_2") (pintype "input+no_connect"))
    )
    (net (code "75") (name "unconnected-(U1-PD2-Pad55)") (class "Default")
      (node (ref "U1") (pin "55") (pinfunction "PD2_55") (pintype "input+no_connect"))
    )
    (net (code "76") (name "unconnected-(U1-VBAT-Pad1)") (class "Default")
      (node (ref "U1") (pin "1") (pinfunction "VBAT_1") (pintype "input+no_connect"))
    )
    (net (code "77") (name "unconnected-(U4-EP-Pad7)") (class "Default")
      (node (ref "U4") (pin "7") (pinfunction "EP_7") (pintype "unspecified+no_connect"))
    )
    (net (code "78") (name "unconnected-(U5-SDO-Pad6)") (class "Default")
      (node (ref "U5") (pin "6") (pinfunction "SDO_6") (pintype "input+no_connect"))
    )
    (net (code "79") (name "unconnected-(U6-NC-Pad1)") (class "Default")
      (node (ref "U6") (pin "1") (pinfunction "NC_1") (pintype "unspecified+no_connect"))
    )
    (net (code "80") (name "unconnected-(U6-NC-Pad2)") (class "Default")
      (node (ref "U6") (pin "2") (pinfunction "NC_2") (pintype "unspecified+no_connect"))
    )
    (net (code "81") (name "unconnected-(U6-NC-Pad3)") (class "Default")
      (node (ref "U6") (pin "3") (pinfunction "NC_3") (pintype "unspecified+no_connect"))
    )
    (net (code "82") (name "unconnected-(U6-NC-Pad6)") (class "Default")
      (node (ref "U6") (pin "6") (pinfunction "NC_6") (pintype "unspecified+no_connect"))
    )
    (net (code "83") (name "unconnected-(U6-NC-Pad11)") (class "Default")
      (node (ref "U6") (pin "11") (pinfunction "NC_11") (pintype "unspecified+no_connect"))
    )
    (net (code "84") (name "unconnected-(U6-NC-Pad12)") (class "Default")
      (node (ref "U6") (pin "12") (pinfunction "NC_12") (pintype "unspecified+no_connect"))
    )
    (net (code "85") (name "unconnected-(U6-TP-Pad9)") (class "Default")
      (node (ref "U6") (pin "9") (pinfunction "TP_9") (pintype "unspecified+no_connect"))
    )
    (net (code "86") (name "unconnected-(U7-NC-Pad3)") (class "Default")
      (node (ref "U7") (pin "3") (pinfunction "NC_3") (pintype "unspecified+no_connect"))
    )
  )
)
